# Clock_Schematic_v_8_no_jumpers.net
KiCad netlist of a schematic drawn in EAGLE
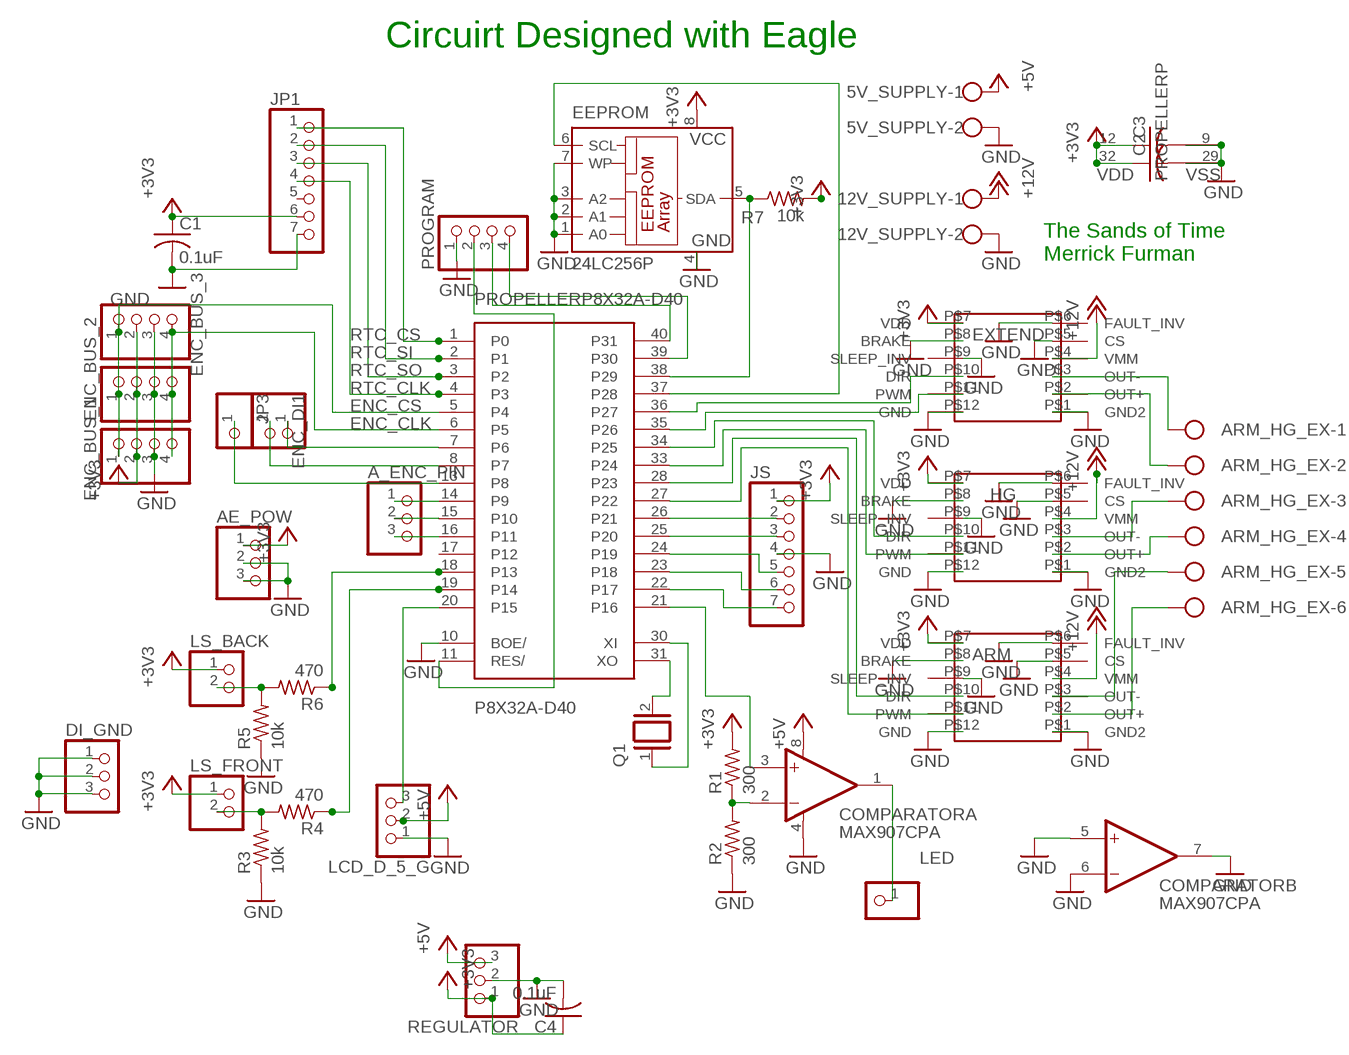
[diagram p0: schematic, sheet 1]

(export (version "E")
  (design (tool "Eeschema 10.0.6"))
  (components
    (comp (ref "5V_SUPPLY")
      (value "W237-102")
      (footprint "eagle-import:W237-102")
      (fields (field (name "MPN") "237-102"))
      (libsource (lib "eagle-import") (part "W237-102"))
    )
    (comp (ref "12V_SUPPLY")
      (value "W237-102")
      (footprint "eagle-import:W237-102")
      (fields (field (name "MPN") "237-102"))
      (libsource (lib "eagle-import") (part "W237-102"))
    )
    (comp (ref "AE_POW")
      (value "PINHD-1X3")
      (footprint "eagle-import:1X03")
      (libsource (lib "eagle-import") (part "PINHD-1X3"))
    )
    (comp (ref "ARM")
      (value "DRV")
      (footprint "eagle-import:DRV")
      (libsource (lib "eagle-import") (part "DRV"))
    )
    (comp (ref "ARM_HG_EX")
      (value "W237-6")
      (footprint "eagle-import:W237-6")
      (libsource (lib "eagle-import") (part "W237-6"))
    )
    (comp (ref "A_ENC_PIN")
      (value "PINHD-1X3")
      (footprint "eagle-import:1X03")
      (libsource (lib "eagle-import") (part "PINHD-1X3"))
    )
    (comp (ref "C1")
      (value "0.1uF")
      (footprint "eagle-import:C050-025X075")
      (libsource (lib "eagle-import") (part "C-US050-025X075"))
    )
    (comp (ref "C2")
      (value "C-US050-025X075")
      (footprint "eagle-import:C050-025X075")
      (libsource (lib "eagle-import") (part "C-US050-025X075"))
    )
    (comp (ref "C3")
      (value "C-US050-025X075")
      (footprint "eagle-import:C050-025X075")
      (libsource (lib "eagle-import") (part "C-US050-025X075"))
    )
    (comp (ref "C4")
      (value "0.1uF")
      (footprint "eagle-import:C025-030X050")
      (libsource (lib "eagle-import") (part "C-US025-030X050"))
    )
    (comp (ref "COMPARATOR")
      (value "MAX907CPA")
      (footprint "eagle-import:DIL08")
      (fields (field (name "MF") "MAXIM") (field (name "SPICEPREFIX") "X"))
      (libsource (lib "eagle-import") (part "MAX907CPA"))
    )
    (comp (ref "DI_GND")
      (value "PINHD-1X3")
      (footprint "eagle-import:1X03")
      (libsource (lib "eagle-import") (part "PINHD-1X3"))
    )
    (comp (ref "EEPROM")
      (value "24LC256P")
      (footprint "eagle-import:DIL8")
      (fields (field (name "MF") "MICROCHIP") (field (name "MPN") "24LC256-E/P"))
      (libsource (lib "eagle-import") (part "24PLC256"))
    )
    (comp (ref "ENC_BUS_1")
      (value "PINHD-1X4")
      (footprint "eagle-import:1X04")
      (libsource (lib "eagle-import") (part "PINHD-1X4"))
    )
    (comp (ref "ENC_BUS_2")
      (value "PINHD-1X4")
      (footprint "eagle-import:1X04")
      (libsource (lib "eagle-import") (part "PINHD-1X4"))
    )
    (comp (ref "ENC_BUS_3")
      (value "PINHD-1X4")
      (footprint "eagle-import:1X04")
      (libsource (lib "eagle-import") (part "PINHD-1X4"))
    )
    (comp (ref "ENC_DI1")
      (value "PINHD-1X2")
      (footprint "eagle-import:1X02")
      (libsource (lib "eagle-import") (part "PINHD-1X2"))
    )
    (comp (ref "EXTEND")
      (value "DRV")
      (footprint "eagle-import:DRV")
      (libsource (lib "eagle-import") (part "DRV"))
    )
    (comp (ref "HG")
      (value "DRV")
      (footprint "eagle-import:DRV")
      (libsource (lib "eagle-import") (part "DRV"))
    )
    (comp (ref "JP1")
      (value "PINHD-1X7")
      (footprint "eagle-import:1X07")
      (libsource (lib "eagle-import") (part "PINHD-1X7"))
    )
    (comp (ref "JP3")
      (value "PINHD-1X1")
      (footprint "eagle-import:1X01")
      (libsource (lib "eagle-import") (part "PINHD-1X1"))
    )
    (comp (ref "JS")
      (value "PINHD-1X7")
      (footprint "eagle-import:1X07")
      (libsource (lib "eagle-import") (part "PINHD-1X7"))
    )
    (comp (ref "LCD_D_5_G")
      (value "PINHD-1X3")
      (footprint "eagle-import:1X03")
      (libsource (lib "eagle-import") (part "PINHD-1X3"))
    )
    (comp (ref "LED")
      (value "PINHD-1X1")
      (footprint "eagle-import:1X01")
      (libsource (lib "eagle-import") (part "PINHD-1X1"))
    )
    (comp (ref "LS_BACK")
      (value "PINHD-1X2")
      (footprint "eagle-import:1X02")
      (libsource (lib "eagle-import") (part "PINHD-1X2"))
    )
    (comp (ref "LS_FRONT")
      (value "PINHD-1X2")
      (footprint "eagle-import:1X02")
      (libsource (lib "eagle-import") (part "PINHD-1X2"))
    )
    (comp (ref "PROGRAM")
      (value "PINHD-1X4")
      (footprint "eagle-import:1X04")
      (libsource (lib "eagle-import") (part "PINHD-1X4"))
    )
    (comp (ref "PROPELLER")
      (value "P8X32A-D40")
      (footprint "eagle-import:P8X32A-D40")
      (libsource (lib "eagle-import") (part "P8X32A-D40"))
    )
    (comp (ref "Q1")
      (value "XTAL/S")
      (footprint "eagle-import:QS")
      (libsource (lib "eagle-import") (part "XTAL/S"))
    )
    (comp (ref "R1")
      (value "300")
      (footprint "eagle-import:0207_10")
      (libsource (lib "eagle-import") (part "R-US_0207/10"))
    )
    (comp (ref "R2")
      (value "300")
      (footprint "eagle-import:0207_10")
      (libsource (lib "eagle-import") (part "R-US_0207/10"))
    )
    (comp (ref "R3")
      (value "10k")
      (footprint "eagle-import:0207_10")
      (libsource (lib "eagle-import") (part "R-US_0207/10"))
    )
    (comp (ref "R4")
      (value "470")
      (footprint "eagle-import:0207_10")
      (libsource (lib "eagle-import") (part "R-US_0207/10"))
    )
    (comp (ref "R5")
      (value "10k")
      (footprint "eagle-import:0207_10")
      (libsource (lib "eagle-import") (part "R-US_0207/10"))
    )
    (comp (ref "R6")
      (value "470")
      (footprint "eagle-import:0207_10")
      (libsource (lib "eagle-import") (part "R-US_0207/10"))
    )
    (comp (ref "R7")
      (value "10k")
      (footprint "eagle-import:0207_10")
      (libsource (lib "eagle-import") (part "R-US_0207/10"))
    )
    (comp (ref "REGULATOR")
      (value "PINHD-1X3")
      (footprint "eagle-import:1X03")
      (libsource (lib "eagle-import") (part "PINHD-1X3"))
    )
  )
  (nets
    (net (code "1") (name "+3V3") (class "Default")
      (node (ref "AE_POW") (pin "1") (pinfunction "1_1") (pintype "passive"))
      (node (ref "ARM") (pin "P$7") (pinfunction "VDD_P$7") (pintype "bidirectional"))
      (node (ref "C1") (pin "1") (pinfunction "1_1") (pintype "passive"))
      (node (ref "C2") (pin "1") (pinfunction "1_1") (pintype "passive"))
      (node (ref "C3") (pin "1") (pinfunction "1_1") (pintype "passive"))
      (node (ref "C4") (pin "1") (pinfunction "1_1") (pintype "passive"))
      (node (ref "EEPROM") (pin "8") (pinfunction "VCC_8") (pintype "power_in"))
      (node (ref "ENC_BUS_1") (pin "2") (pinfunction "2_2") (pintype "passive"))
      (node (ref "ENC_BUS_2") (pin "2") (pinfunction "2_2") (pintype "passive"))
      (node (ref "ENC_BUS_3") (pin "2") (pinfunction "2_2") (pintype "passive"))
      (node (ref "EXTEND") (pin "P$7") (pinfunction "VDD_P$7") (pintype "bidirectional"))
      (node (ref "HG") (pin "P$7") (pinfunction "VDD_P$7") (pintype "bidirectional"))
      (node (ref "JP1") (pin "6") (pinfunction "6_6") (pintype "passive"))
      (node (ref "JS") (pin "1") (pinfunction "1_1") (pintype "passive"))
      (node (ref "LS_BACK") (pin "1") (pinfunction "1_1") (pintype "passive"))
      (node (ref "LS_FRONT") (pin "1") (pinfunction "1_1") (pintype "passive"))
      (node (ref "PROPELLER") (pin "12") (pinfunction "VDD_12") (pintype "power_in"))
      (node (ref "PROPELLER") (pin "32") (pinfunction "VDD_32") (pintype "power_in"))
      (node (ref "R1") (pin "2") (pinfunction "2_2") (pintype "passive"))
      (node (ref "R7") (pin "2") (pinfunction "2_2") (pintype "passive"))
      (node (ref "REGULATOR") (pin "1") (pinfunction "1_1") (pintype "passive"))
    )
    (net (code "2") (name "+5V") (class "Default")
      (node (ref "5V_SUPPLY") (pin "1") (pinfunction "KL_1") (pintype "passive"))
      (node (ref "COMPARATOR") (pin "8") (pinfunction "V+_8") (pintype "power_in"))
      (node (ref "LCD_D_5_G") (pin "2") (pinfunction "2_2") (pintype "passive"))
      (node (ref "REGULATOR") (pin "3") (pinfunction "3_3") (pintype "passive"))
    )
    (net (code "3") (name "+12V") (class "Default")
      (node (ref "12V_SUPPLY") (pin "1") (pinfunction "KL_1") (pintype "passive"))
      (node (ref "ARM") (pin "P$4") (pinfunction "VMM_P$4") (pintype "bidirectional"))
      (node (ref "EXTEND") (pin "P$4") (pinfunction "VMM_P$4") (pintype "bidirectional"))
      (node (ref "HG") (pin "P$4") (pinfunction "VMM_P$4") (pintype "bidirectional"))
    )
    (net (code "4") (name "/ENC_CLK") (class "Default")
      (node (ref "ENC_BUS_1") (pin "4") (pinfunction "4_4") (pintype "passive"))
      (node (ref "ENC_BUS_2") (pin "4") (pinfunction "4_4") (pintype "passive"))
      (node (ref "ENC_BUS_3") (pin "4") (pinfunction "4_4") (pintype "passive"))
      (node (ref "PROPELLER") (pin "6") (pinfunction "P5_6") (pintype "bidirectional"))
    )
    (net (code "5") (name "/ENC_CS") (class "Default")
      (node (ref "ENC_BUS_1") (pin "1") (pinfunction "1_1") (pintype "passive"))
      (node (ref "ENC_BUS_2") (pin "1") (pinfunction "1_1") (pintype "passive"))
      (node (ref "ENC_BUS_3") (pin "1") (pinfunction "1_1") (pintype "passive"))
      (node (ref "PROPELLER") (pin "5") (pinfunction "P4_5") (pintype "bidirectional"))
    )
    (net (code "6") (name "/RTC_CLK") (class "Default")
      (node (ref "JP1") (pin "4") (pinfunction "4_4") (pintype "passive"))
      (node (ref "PROPELLER") (pin "4") (pinfunction "P3_4") (pintype "bidirectional"))
    )
    (net (code "7") (name "/RTC_CS") (class "Default")
      (node (ref "JP1") (pin "1") (pinfunction "1_1") (pintype "passive"))
      (node (ref "PROPELLER") (pin "1") (pinfunction "P0_1") (pintype "bidirectional"))
    )
    (net (code "8") (name "/RTC_SI") (class "Default")
      (node (ref "JP1") (pin "2") (pinfunction "2_2") (pintype "passive"))
      (node (ref "PROPELLER") (pin "2") (pinfunction "P1_2") (pintype "bidirectional"))
    )
    (net (code "9") (name "/RTC_SO") (class "Default")
      (node (ref "JP1") (pin "3") (pinfunction "3_3") (pintype "passive"))
      (node (ref "PROPELLER") (pin "3") (pinfunction "P2_3") (pintype "bidirectional"))
    )
    (net (code "10") (name "GND") (class "Default")
      (node (ref "12V_SUPPLY") (pin "2") (pinfunction "KL_2") (pintype "passive"))
      (node (ref "5V_SUPPLY") (pin "2") (pinfunction "KL_2") (pintype "passive"))
      (node (ref "AE_POW") (pin "2") (pinfunction "2_2") (pintype "passive"))
      (node (ref "AE_POW") (pin "3") (pinfunction "3_3") (pintype "passive"))
      (node (ref "ARM") (pin "P$1") (pinfunction "GND2_P$1") (pintype "bidirectional"))
      (node (ref "ARM") (pin "P$12") (pinfunction "GND_P$12") (pintype "bidirectional"))
      (node (ref "ARM") (pin "P$5") (pinfunction "CS_P$5") (pintype "bidirectional"))
      (node (ref "ARM") (pin "P$6") (pinfunction "FAULT_INV_P$6") (pintype "bidirectional"))
      (node (ref "ARM") (pin "P$8") (pinfunction "BRAKE_P$8") (pintype "bidirectional"))
      (node (ref "ARM") (pin "P$9") (pinfunction "SLEEP_INV_P$9") (pintype "bidirectional"))
      (node (ref "C1") (pin "2") (pinfunction "2_2") (pintype "passive"))
      (node (ref "C2") (pin "2") (pinfunction "2_2") (pintype "passive"))
      (node (ref "C3") (pin "2") (pinfunction "2_2") (pintype "passive"))
      (node (ref "C4") (pin "2") (pinfunction "2_2") (pintype "passive"))
      (node (ref "COMPARATOR") (pin "4") (pinfunction "V-_4") (pintype "power_in"))
      (node (ref "COMPARATOR") (pin "5") (pinfunction "+IN_5") (pintype "input"))
      (node (ref "COMPARATOR") (pin "6") (pinfunction "-IN_6") (pintype "input"))
      (node (ref "COMPARATOR") (pin "7") (pinfunction "OUT_7") (pintype "output"))
      (node (ref "DI_GND") (pin "1") (pinfunction "1_1") (pintype "passive"))
      (node (ref "DI_GND") (pin "2") (pinfunction "2_2") (pintype "passive"))
      (node (ref "DI_GND") (pin "3") (pinfunction "3_3") (pintype "passive"))
      (node (ref "EEPROM") (pin "1") (pinfunction "A0_1") (pintype "input"))
      (node (ref "EEPROM") (pin "2") (pinfunction "A1_2") (pintype "input"))
      (node (ref "EEPROM") (pin "3") (pinfunction "A2_3") (pintype "input"))
      (node (ref "EEPROM") (pin "4") (pinfunction "GND_4") (pintype "power_in"))
      (node (ref "EEPROM") (pin "7") (pinfunction "WP_7") (pintype "input"))
      (node (ref "ENC_BUS_1") (pin "3") (pinfunction "3_3") (pintype "passive"))
      (node (ref "ENC_BUS_2") (pin "3") (pinfunction "3_3") (pintype "passive"))
      (node (ref "ENC_BUS_3") (pin "3") (pinfunction "3_3") (pintype "passive"))
      (node (ref "EXTEND") (pin "P$1") (pinfunction "GND2_P$1") (pintype "bidirectional"))
      (node (ref "EXTEND") (pin "P$12") (pinfunction "GND_P$12") (pintype "bidirectional"))
      (node (ref "EXTEND") (pin "P$5") (pinfunction "CS_P$5") (pintype "bidirectional"))
      (node (ref "EXTEND") (pin "P$6") (pinfunction "FAULT_INV_P$6") (pintype "bidirectional"))
      (node (ref "EXTEND") (pin "P$8") (pinfunction "BRAKE_P$8") (pintype "bidirectional"))
      (node (ref "EXTEND") (pin "P$9") (pinfunction "SLEEP_INV_P$9") (pintype "bidirectional"))
      (node (ref "HG") (pin "P$1") (pinfunction "GND2_P$1") (pintype "bidirectional"))
      (node (ref "HG") (pin "P$12") (pinfunction "GND_P$12") (pintype "bidirectional"))
      (node (ref "HG") (pin "P$5") (pinfunction "CS_P$5") (pintype "bidirectional"))
      (node (ref "HG") (pin "P$6") (pinfunction "FAULT_INV_P$6") (pintype "bidirectional"))
      (node (ref "HG") (pin "P$8") (pinfunction "BRAKE_P$8") (pintype "bidirectional"))
      (node (ref "HG") (pin "P$9") (pinfunction "SLEEP_INV_P$9") (pintype "bidirectional"))
      (node (ref "JP1") (pin "7") (pinfunction "7_7") (pintype "passive"))
      (node (ref "JS") (pin "4") (pinfunction "4_4") (pintype "passive"))
      (node (ref "LCD_D_5_G") (pin "1") (pinfunction "1_1") (pintype "passive"))
      (node (ref "PROGRAM") (pin "1") (pinfunction "1_1") (pintype "passive"))
      (node (ref "PROPELLER") (pin "10") (pinfunction "BOE/_10") (pintype "input"))
      (node (ref "PROPELLER") (pin "29") (pinfunction "VSS_29") (pintype "power_in"))
      (node (ref "PROPELLER") (pin "9") (pinfunction "VSS_9") (pintype "power_in"))
      (node (ref "R2") (pin "1") (pinfunction "1_1") (pintype "passive"))
      (node (ref "R3") (pin "1") (pinfunction "1_1") (pintype "passive"))
      (node (ref "R5") (pin "1") (pinfunction "1_1") (pintype "passive"))
      (node (ref "REGULATOR") (pin "2") (pinfunction "2_2") (pintype "passive"))
    )
    (net (code "11") (name "Net-(ARM-DIR)") (class "Default")
      (node (ref "ARM") (pin "P$10") (pinfunction "DIR_P$10") (pintype "bidirectional"))
      (node (ref "PROPELLER") (pin "28") (pinfunction "P23_28") (pintype "bidirectional"))
    )
    (net (code "12") (name "Net-(ARM-OUT+)") (class "Default")
      (node (ref "ARM") (pin "P$2") (pinfunction "OUT+_P$2") (pintype "bidirectional"))
      (node (ref "ARM_HG_EX") (pin "6") (pinfunction "KL_6") (pintype "passive"))
    )
    (net (code "13") (name "Net-(ARM-OUT-)") (class "Default")
      (node (ref "ARM") (pin "P$3") (pinfunction "OUT-_P$3") (pintype "bidirectional"))
      (node (ref "ARM_HG_EX") (pin "5") (pinfunction "KL_5") (pintype "passive"))
    )
    (net (code "14") (name "Net-(ARM-PWM)") (class "Default")
      (node (ref "ARM") (pin "P$11") (pinfunction "PWM_P$11") (pintype "bidirectional"))
      (node (ref "PROPELLER") (pin "27") (pinfunction "P22_27") (pintype "bidirectional"))
    )
    (net (code "15") (name "Net-(ARM_HG_EXA-KL)") (class "Default")
      (node (ref "ARM_HG_EX") (pin "1") (pinfunction "KL_1") (pintype "passive"))
      (node (ref "EXTEND") (pin "P$3") (pinfunction "OUT-_P$3") (pintype "bidirectional"))
    )
    (net (code "16") (name "Net-(ARM_HG_EXB-KL)") (class "Default")
      (node (ref "ARM_HG_EX") (pin "2") (pinfunction "KL_2") (pintype "passive"))
      (node (ref "EXTEND") (pin "P$2") (pinfunction "OUT+_P$2") (pintype "bidirectional"))
    )
    (net (code "17") (name "Net-(ARM_HG_EXC-KL)") (class "Default")
      (node (ref "ARM_HG_EX") (pin "3") (pinfunction "KL_3") (pintype "passive"))
      (node (ref "HG") (pin "P$3") (pinfunction "OUT-_P$3") (pintype "bidirectional"))
    )
    (net (code "18") (name "Net-(ARM_HG_EXD-KL)") (class "Default")
      (node (ref "ARM_HG_EX") (pin "4") (pinfunction "KL_4") (pintype "passive"))
      (node (ref "HG") (pin "P$2") (pinfunction "OUT+_P$2") (pintype "bidirectional"))
    )
    (net (code "19") (name "Net-(COMPARATORA-+IN)") (class "Default")
      (node (ref "COMPARATOR") (pin "3") (pinfunction "+IN_3") (pintype "input"))
      (node (ref "PROPELLER") (pin "21") (pinfunction "P16_21") (pintype "bidirectional"))
    )
    (net (code "20") (name "Net-(COMPARATORA--IN)") (class "Default")
      (node (ref "COMPARATOR") (pin "2") (pinfunction "-IN_2") (pintype "input"))
      (node (ref "R1") (pin "1") (pinfunction "1_1") (pintype "passive"))
      (node (ref "R2") (pin "2") (pinfunction "2_2") (pintype "passive"))
    )
    (net (code "21") (name "Net-(COMPARATORA-OUT)") (class "Default")
      (node (ref "COMPARATOR") (pin "1") (pinfunction "OUT_1") (pintype "output"))
      (node (ref "LED") (pin "1") (pinfunction "1_1") (pintype "passive"))
    )
    (net (code "22") (name "Net-(EEPROM-SCL)") (class "Default")
      (node (ref "EEPROM") (pin "6") (pinfunction "SCL_6") (pintype "input"))
      (node (ref "PROPELLER") (pin "37") (pinfunction "P28_37") (pintype "bidirectional"))
    )
    (net (code "23") (name "Net-(EEPROM-SDA)") (class "Default")
      (node (ref "EEPROM") (pin "5") (pinfunction "SDA_5") (pintype "bidirectional"))
      (node (ref "PROPELLER") (pin "38") (pinfunction "P29_38") (pintype "bidirectional"))
      (node (ref "R7") (pin "1") (pinfunction "1_1") (pintype "passive"))
    )
    (net (code "24") (name "Net-(EXTEND-DIR)") (class "Default")
      (node (ref "EXTEND") (pin "P$10") (pinfunction "DIR_P$10") (pintype "bidirectional"))
      (node (ref "PROPELLER") (pin "36") (pinfunction "P27_36") (pintype "bidirectional"))
    )
    (net (code "25") (name "Net-(EXTEND-PWM)") (class "Default")
      (node (ref "EXTEND") (pin "P$11") (pinfunction "PWM_P$11") (pintype "bidirectional"))
      (node (ref "PROPELLER") (pin "35") (pinfunction "P26_35") (pintype "bidirectional"))
    )
    (net (code "26") (name "Net-(HG-DIR)") (class "Default")
      (node (ref "HG") (pin "P$10") (pinfunction "DIR_P$10") (pintype "bidirectional"))
      (node (ref "PROPELLER") (pin "34") (pinfunction "P25_34") (pintype "bidirectional"))
    )
    (net (code "27") (name "Net-(HG-PWM)") (class "Default")
      (node (ref "HG") (pin "P$11") (pinfunction "PWM_P$11") (pintype "bidirectional"))
      (node (ref "PROPELLER") (pin "33") (pinfunction "P24_33") (pintype "bidirectional"))
    )
    (net (code "28") (name "Net-(LS_BACK-Pad2)") (class "Default")
      (node (ref "LS_BACK") (pin "2") (pinfunction "2_2") (pintype "passive"))
      (node (ref "R5") (pin "2") (pinfunction "2_2") (pintype "passive"))
      (node (ref "R6") (pin "2") (pinfunction "2_2") (pintype "passive"))
    )
    (net (code "29") (name "Net-(LS_FRONT-Pad2)") (class "Default")
      (node (ref "LS_FRONT") (pin "2") (pinfunction "2_2") (pintype "passive"))
      (node (ref "R3") (pin "2") (pinfunction "2_2") (pintype "passive"))
      (node (ref "R4") (pin "2") (pinfunction "2_2") (pintype "passive"))
    )
    (net (code "30") (name "Net-(PROPELLERB-P6)") (class "Default")
      (node (ref "ENC_DI1") (pin "1") (pinfunction "1_1") (pintype "passive"))
      (node (ref "PROPELLER") (pin "7") (pinfunction "P6_7") (pintype "bidirectional"))
    )
    (net (code "31") (name "Net-(PROPELLERB-P7)") (class "Default")
      (node (ref "ENC_DI1") (pin "2") (pinfunction "2_2") (pintype "passive"))
      (node (ref "PROPELLER") (pin "8") (pinfunction "P7_8") (pintype "bidirectional"))
    )
    (net (code "32") (name "Net-(PROPELLERB-P8)") (class "Default")
      (node (ref "JP3") (pin "1") (pinfunction "1_1") (pintype "passive"))
      (node (ref "PROPELLER") (pin "13") (pinfunction "P8_13") (pintype "bidirectional"))
    )
    (net (code "33") (name "Net-(PROPELLERB-P9)") (class "Default")
      (node (ref "A_ENC_PIN") (pin "1") (pinfunction "1_1") (pintype "passive"))
      (node (ref "PROPELLER") (pin "14") (pinfunction "P9_14") (pintype "bidirectional"))
    )
    (net (code "34") (name "Net-(PROPELLERB-P10)") (class "Default")
      (node (ref "A_ENC_PIN") (pin "2") (pinfunction "2_2") (pintype "passive"))
      (node (ref "PROPELLER") (pin "15") (pinfunction "P10_15") (pintype "bidirectional"))
    )
    (net (code "35") (name "Net-(PROPELLERB-P11)") (class "Default")
      (node (ref "A_ENC_PIN") (pin "3") (pinfunction "3_3") (pintype "passive"))
      (node (ref "PROPELLER") (pin "16") (pinfunction "P11_16") (pintype "bidirectional"))
    )
    (net (code "36") (name "Net-(PROPELLERB-P13)") (class "Default")
      (node (ref "PROPELLER") (pin "18") (pinfunction "P13_18") (pintype "bidirectional"))
      (node (ref "R6") (pin "1") (pinfunction "1_1") (pintype "passive"))
    )
    (net (code "37") (name "Net-(PROPELLERB-P14)") (class "Default")
      (node (ref "PROPELLER") (pin "19") (pinfunction "P14_19") (pintype "bidirectional"))
      (node (ref "R4") (pin "1") (pinfunction "1_1") (pintype "passive"))
    )
    (net (code "38") (name "Net-(PROPELLERB-P15)") (class "Default")
      (node (ref "LCD_D_5_G") (pin "3") (pinfunction "3_3") (pintype "passive"))
      (node (ref "PROPELLER") (pin "20") (pinfunction "P15_20") (pintype "bidirectional"))
    )
    (net (code "39") (name "Net-(PROPELLERB-P17)") (class "Default")
      (node (ref "JS") (pin "7") (pinfunction "7_7") (pintype "passive"))
      (node (ref "PROPELLER") (pin "22") (pinfunction "P17_22") (pintype "bidirectional"))
    )
    (net (code "40") (name "Net-(PROPELLERB-P18)") (class "Default")
      (node (ref "JS") (pin "6") (pinfunction "6_6") (pintype "passive"))
      (node (ref "PROPELLER") (pin "23") (pinfunction "P18_23") (pintype "bidirectional"))
    )
    (net (code "41") (name "Net-(PROPELLERB-P19)") (class "Default")
      (node (ref "JS") (pin "5") (pinfunction "5_5") (pintype "passive"))
      (node (ref "PROPELLER") (pin "24") (pinfunction "P19_24") (pintype "bidirectional"))
    )
    (net (code "42") (name "Net-(PROPELLERB-P20)") (class "Default")
      (node (ref "JS") (pin "3") (pinfunction "3_3") (pintype "passive"))
      (node (ref "PROPELLER") (pin "25") (pinfunction "P20_25") (pintype "bidirectional"))
    )
    (net (code "43") (name "Net-(PROPELLERB-P21)") (class "Default")
      (node (ref "JS") (pin "2") (pinfunction "2_2") (pintype "passive"))
      (node (ref "PROPELLER") (pin "26") (pinfunction "P21_26") (pintype "bidirectional"))
    )
    (net (code "44") (name "Net-(PROPELLERB-P30)") (class "Default")
      (node (ref "PROGRAM") (pin "4") (pinfunction "4_4") (pintype "passive"))
      (node (ref "PROPELLER") (pin "39") (pinfunction "P30_39") (pintype "bidirectional"))
    )
    (net (code "45") (name "Net-(PROPELLERB-P31)") (class "Default")
      (node (ref "PROGRAM") (pin "3") (pinfunction "3_3") (pintype "passive"))
      (node (ref "PROPELLER") (pin "40") (pinfunction "P31_40") (pintype "bidirectional"))
    )
    (net (code "46") (name "Net-(PROPELLERB-RES{slash})") (class "Default")
      (node (ref "PROGRAM") (pin "2") (pinfunction "2_2") (pintype "passive"))
      (node (ref "PROPELLER") (pin "11") (pinfunction "RES/_11") (pintype "bidirectional"))
    )
    (net (code "47") (name "Net-(PROPELLERB-XI)") (class "Default")
      (node (ref "PROPELLER") (pin "30") (pinfunction "XI_30") (pintype "input"))
      (node (ref "Q1") (pin "1") (pinfunction "1_1") (pintype "passive"))
    )
    (net (code "48") (name "Net-(PROPELLERB-XO)") (class "Default")
      (node (ref "PROPELLER") (pin "31") (pinfunction "XO_31") (pintype "output"))
      (node (ref "Q1") (pin "2") (pinfunction "2_2") (pintype "passive"))
    )
    (net (code "49") (name "unconnected-(JP1-Pad5)") (class "Default")
      (node (ref "JP1") (pin "5") (pinfunction "5_5") (pintype "passive"))
    )
    (net (code "50") (name "unconnected-(PROPELLERB-P12-Pad17)") (class "Default")
      (node (ref "PROPELLER") (pin "17") (pinfunction "P12_17") (pintype "bidirectional"))
    )
  )
)
